# mainboard.net
KiCad netlist of a schematic drawn in EAGLE
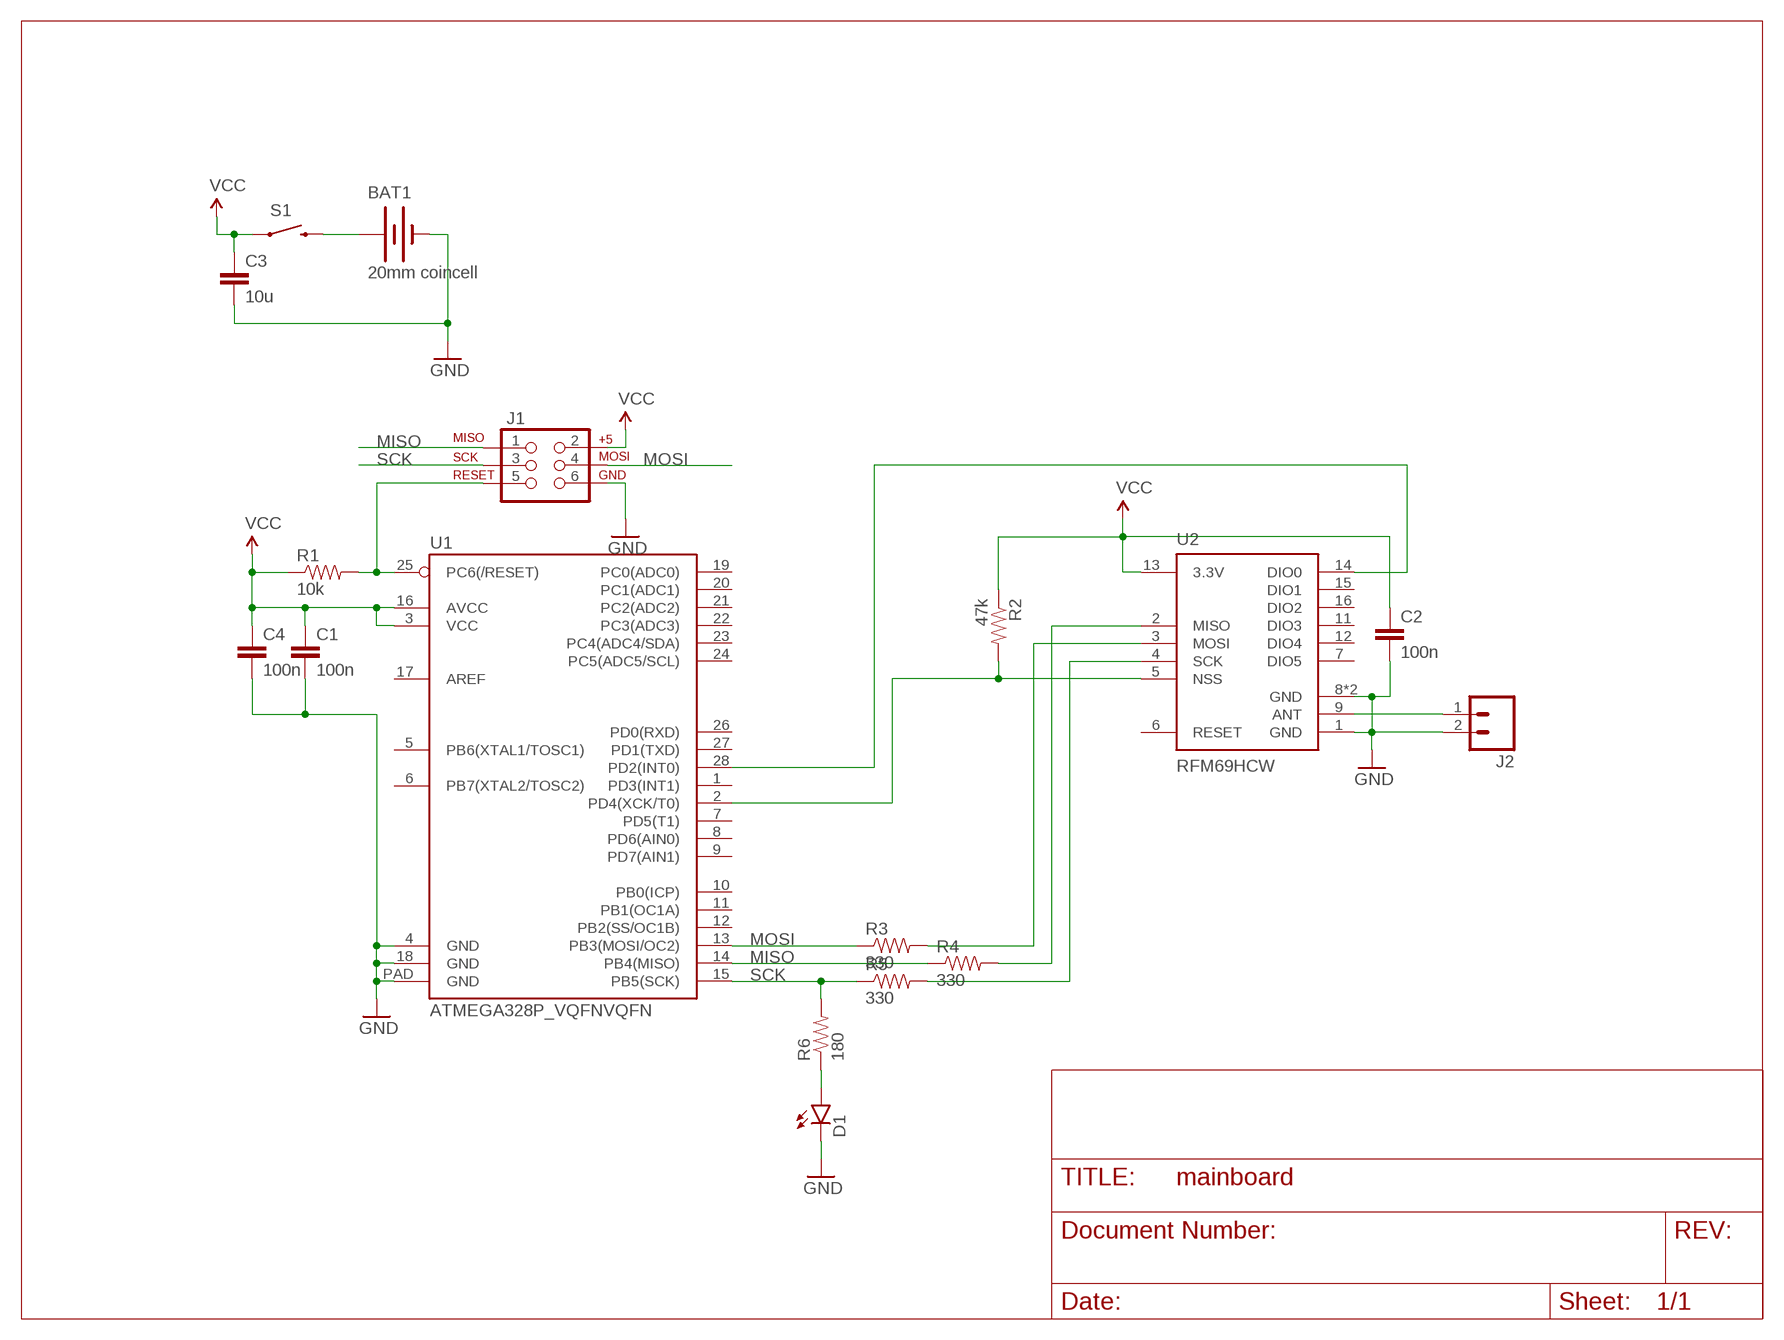
[diagram p0: schematic, sheet 1]

(export (version "E")
  (design (tool "Eeschema 10.0.6"))
  (components
    (comp (ref "BAT1")
      (value "20mm coincell")
      (footprint "eagle-import:BATTCON_20MM_4LEGS")
      (libsource (lib "eagle-import") (part "BATTERY20MM_4LEGS"))
    )
    (comp (ref "C1")
      (value "100n")
      (footprint "eagle-import:0603-CAP")
      (libsource (lib "eagle-import") (part "CAP0603-CAP"))
    )
    (comp (ref "C2")
      (value "100n")
      (footprint "eagle-import:0603-CAP")
      (libsource (lib "eagle-import") (part "CAP0603-CAP"))
    )
    (comp (ref "C3")
      (value "10u")
      (footprint "eagle-import:1206")
      (libsource (lib "eagle-import") (part "CAP1206"))
    )
    (comp (ref "C4")
      (value "100n")
      (footprint "eagle-import:0603-CAP")
      (libsource (lib "eagle-import") (part "CAP0603-CAP"))
    )
    (comp (ref "D1")
      (value "LED0603")
      (footprint "eagle-import:LED-0603")
      (libsource (lib "eagle-import") (part "LED0603"))
    )
    (comp (ref "J1")
      (value "AVR_SPI_PRG_6PTH")
      (footprint "eagle-import:2X3")
      (libsource (lib "eagle-import") (part "AVR_SPI_PRG_6PTH"))
    )
    (comp (ref "J2")
      (value "M02PTH")
      (footprint "eagle-import:1X02")
      (libsource (lib "eagle-import") (part "M02PTH"))
    )
    (comp (ref "R1")
      (value "10k")
      (footprint "eagle-import:0603-RES")
      (libsource (lib "eagle-import") (part "RESISTOR0603-RES"))
    )
    (comp (ref "R2")
      (value "47k")
      (footprint "eagle-import:0603-RES")
      (libsource (lib "eagle-import") (part "RESISTOR0603-RES"))
    )
    (comp (ref "R3")
      (value "330")
      (footprint "eagle-import:0603-RES")
      (libsource (lib "eagle-import") (part "RESISTOR0603-RES"))
    )
    (comp (ref "R4")
      (value "330")
      (footprint "eagle-import:0603-RES")
      (libsource (lib "eagle-import") (part "RESISTOR0603-RES"))
    )
    (comp (ref "R5")
      (value "330")
      (footprint "eagle-import:0603-RES")
      (libsource (lib "eagle-import") (part "RESISTOR0603-RES"))
    )
    (comp (ref "R6")
      (value "180")
      (footprint "eagle-import:0603-RES")
      (libsource (lib "eagle-import") (part "RESISTOR0603-RES"))
    )
    (comp (ref "S1")
      (value "SWITCH-MOMENTARY-2PTH")
      (footprint "eagle-import:TACTILE-PTH")
      (libsource (lib "eagle-import") (part "SWITCH-MOMENTARY-2PTH"))
    )
    (comp (ref "U1")
      (value "ATMEGA328P_VQFNVQFN")
      (footprint "eagle-import:VQFN-28")
      (libsource (lib "eagle-import") (part "ATMEGA328P_VQFNVQFN"))
    )
    (comp (ref "U2")
      (value "RFM69HCW")
      (footprint "eagle-import:RFM69HCW-XXXS2")
      (libsource (lib "eagle-import") (part "RFM69HCW"))
    )
  )
  (nets
    (net (code "1") (name "/MISO") (class "Default")
      (node (ref "J1") (pin "1") (pinfunction "1_1") (pintype "passive"))
      (node (ref "R4") (pin "1") (pinfunction "1_1") (pintype "passive"))
      (node (ref "U1") (pin "14") (pinfunction "PB4(MISO)_14") (pintype "bidirectional"))
    )
    (net (code "2") (name "/MOSI") (class "Default")
      (node (ref "J1") (pin "4") (pinfunction "4_4") (pintype "passive"))
      (node (ref "R3") (pin "1") (pinfunction "1_1") (pintype "passive"))
      (node (ref "U1") (pin "13") (pinfunction "PB3(MOSI/OC2)_13") (pintype "bidirectional"))
    )
    (net (code "3") (name "/SCK") (class "Default")
      (node (ref "J1") (pin "3") (pinfunction "3_3") (pintype "passive"))
      (node (ref "R5") (pin "1") (pinfunction "1_1") (pintype "passive"))
      (node (ref "R6") (pin "2") (pinfunction "2_2") (pintype "passive"))
      (node (ref "U1") (pin "15") (pinfunction "PB5(SCK)_15") (pintype "bidirectional"))
    )
    (net (code "4") (name "GND") (class "Default")
      (node (ref "BAT1") (pin "NEGATIVE") (pinfunction "-_NEGATIVE") (pintype "power_in"))
      (node (ref "C1") (pin "2") (pinfunction "2_2") (pintype "passive"))
      (node (ref "C2") (pin "2") (pinfunction "2_2") (pintype "passive"))
      (node (ref "C3") (pin "2") (pinfunction "2_2") (pintype "passive"))
      (node (ref "C4") (pin "2") (pinfunction "2_2") (pintype "passive"))
      (node (ref "D1") (pin "C") (pinfunction "C_C") (pintype "passive"))
      (node (ref "J1") (pin "6") (pinfunction "6_6") (pintype "passive"))
      (node (ref "J2") (pin "2") (pinfunction "2_2") (pintype "passive"))
      (node (ref "U1") (pin "18") (pinfunction "GND_18") (pintype "bidirectional"))
      (node (ref "U1") (pin "4") (pinfunction "GND_4") (pintype "bidirectional"))
      (node (ref "U1") (pin "PAD") (pinfunction "GND_PAD") (pintype "bidirectional"))
      (node (ref "U2") (pin "1") (pinfunction "GND_1") (pintype "power_in"))
      (node (ref "U2") (pin "10") (pinfunction "GND_10") (pintype "power_in"))
      (node (ref "U2") (pin "8") (pinfunction "GND_8") (pintype "power_in"))
    )
    (net (code "5") (name "Net-(D1-PadA)") (class "Default")
      (node (ref "D1") (pin "A") (pinfunction "A_A") (pintype "passive"))
      (node (ref "R6") (pin "1") (pinfunction "1_1") (pintype "passive"))
    )
    (net (code "6") (name "Net-(S1-2)") (class "Default")
      (node (ref "BAT1") (pin "POSITIVE@1") (pinfunction "+_POSITIVE@1") (pintype "power_in"))
      (node (ref "BAT1") (pin "POSITIVE@2") (pinfunction "+_POSITIVE@2") (pintype "power_in"))
      (node (ref "BAT1") (pin "POSITIVE@3") (pinfunction "+_POSITIVE@3") (pintype "power_in"))
      (node (ref "BAT1") (pin "POSITIVE@4") (pinfunction "+_POSITIVE@4") (pintype "power_in"))
      (node (ref "S1") (pin "3") (pinfunction "2_3") (pintype "passive"))
    )
    (net (code "7") (name "Net-(U1-PC6({slash}RESET))") (class "Default")
      (node (ref "J1") (pin "5") (pinfunction "5_5") (pintype "passive"))
      (node (ref "R1") (pin "2") (pinfunction "2_2") (pintype "passive"))
      (node (ref "U1") (pin "25") (pinfunction "PC6(/RESET)_25") (pintype "bidirectional"))
    )
    (net (code "8") (name "Net-(U1-PD2(INT0))") (class "Default")
      (node (ref "U1") (pin "28") (pinfunction "PD2(INT0)_28") (pintype "bidirectional"))
      (node (ref "U2") (pin "14") (pinfunction "DIO0_14") (pintype "bidirectional"))
    )
    (net (code "9") (name "Net-(U1-PD4(XCK{slash}T0))") (class "Default")
      (node (ref "R2") (pin "2") (pinfunction "2_2") (pintype "passive"))
      (node (ref "U1") (pin "2") (pinfunction "PD4(XCK/T0)_2") (pintype "bidirectional"))
      (node (ref "U2") (pin "5") (pinfunction "NSS_5") (pintype "input"))
    )
    (net (code "10") (name "Net-(U2-ANT)") (class "Default")
      (node (ref "J2") (pin "1") (pinfunction "1_1") (pintype "passive"))
      (node (ref "U2") (pin "9") (pinfunction "ANT_9") (pintype "passive"))
    )
    (net (code "11") (name "Net-(U2-MISO)") (class "Default")
      (node (ref "R4") (pin "2") (pinfunction "2_2") (pintype "passive"))
      (node (ref "U2") (pin "2") (pinfunction "MISO_2") (pintype "bidirectional"))
    )
    (net (code "12") (name "Net-(U2-MOSI)") (class "Default")
      (node (ref "R3") (pin "2") (pinfunction "2_2") (pintype "passive"))
      (node (ref "U2") (pin "3") (pinfunction "MOSI_3") (pintype "input"))
    )
    (net (code "13") (name "Net-(U2-SCK)") (class "Default")
      (node (ref "R5") (pin "2") (pinfunction "2_2") (pintype "passive"))
      (node (ref "U2") (pin "4") (pinfunction "SCK_4") (pintype "input"))
    )
    (net (code "14") (name "VCC") (class "Default")
      (node (ref "C1") (pin "1") (pinfunction "1_1") (pintype "passive"))
      (node (ref "C2") (pin "1") (pinfunction "1_1") (pintype "passive"))
      (node (ref "C3") (pin "1") (pinfunction "1_1") (pintype "passive"))
      (node (ref "C4") (pin "1") (pinfunction "1_1") (pintype "passive"))
      (node (ref "J1") (pin "2") (pinfunction "2_2") (pintype "passive"))
      (node (ref "R1") (pin "1") (pinfunction "1_1") (pintype "passive"))
      (node (ref "R2") (pin "1") (pinfunction "1_1") (pintype "passive"))
      (node (ref "S1") (pin "1") (pinfunction "1_1") (pintype "passive"))
      (node (ref "U1") (pin "16") (pinfunction "AVCC_16") (pintype "bidirectional"))
      (node (ref "U1") (pin "3") (pinfunction "VCC_3") (pintype "bidirectional"))
      (node (ref "U2") (pin "13") (pinfunction "3.3V_13") (pintype "power_in"))
    )
    (net (code "15") (name "unconnected-(U1-AREF-Pad17)") (class "Default")
      (node (ref "U1") (pin "17") (pinfunction "AREF_17") (pintype "bidirectional"))
    )
    (net (code "16") (name "unconnected-(U1-PB0(ICP)-Pad10)") (class "Default")
      (node (ref "U1") (pin "10") (pinfunction "PB0(ICP)_10") (pintype "bidirectional"))
    )
    (net (code "17") (name "unconnected-(U1-PB1(OC1A)-Pad11)") (class "Default")
      (node (ref "U1") (pin "11") (pinfunction "PB1(OC1A)_11") (pintype "bidirectional"))
    )
    (net (code "18") (name "unconnected-(U1-PB2(SS{slash}OC1B)-Pad12)") (class "Default")
      (node (ref "U1") (pin "12") (pinfunction "PB2(SS/OC1B)_12") (pintype "bidirectional"))
    )
    (net (code "19") (name "unconnected-(U1-PB6(XTAL1{slash}TOSC1)-Pad5)") (class "Default")
      (node (ref "U1") (pin "5") (pinfunction "PB6(XTAL1/TOSC1)_5") (pintype "bidirectional"))
    )
    (net (code "20") (name "unconnected-(U1-PB7(XTAL2{slash}TOSC2)-Pad6)") (class "Default")
      (node (ref "U1") (pin "6") (pinfunction "PB7(XTAL2/TOSC2)_6") (pintype "bidirectional"))
    )
    (net (code "21") (name "unconnected-(U1-PC0(ADC0)-Pad19)") (class "Default")
      (node (ref "U1") (pin "19") (pinfunction "PC0(ADC0)_19") (pintype "bidirectional"))
    )
    (net (code "22") (name "unconnected-(U1-PC1(ADC1)-Pad20)") (class "Default")
      (node (ref "U1") (pin "20") (pinfunction "PC1(ADC1)_20") (pintype "bidirectional"))
    )
    (net (code "23") (name "unconnected-(U1-PC2(ADC2)-Pad21)") (class "Default")
      (node (ref "U1") (pin "21") (pinfunction "PC2(ADC2)_21") (pintype "bidirectional"))
    )
    (net (code "24") (name "unconnected-(U1-PC3(ADC3)-Pad22)") (class "Default")
      (node (ref "U1") (pin "22") (pinfunction "PC3(ADC3)_22") (pintype "bidirectional"))
    )
    (net (code "25") (name "unconnected-(U1-PC4(ADC4{slash}SDA)-Pad23)") (class "Default")
      (node (ref "U1") (pin "23") (pinfunction "PC4(ADC4/SDA)_23") (pintype "bidirectional"))
    )
    (net (code "26") (name "unconnected-(U1-PC5(ADC5{slash}SCL)-Pad24)") (class "Default")
      (node (ref "U1") (pin "24") (pinfunction "PC5(ADC5/SCL)_24") (pintype "bidirectional"))
    )
    (net (code "27") (name "unconnected-(U1-PD0(RXD)-Pad26)") (class "Default")
      (node (ref "U1") (pin "26") (pinfunction "PD0(RXD)_26") (pintype "bidirectional"))
    )
    (net (code "28") (name "unconnected-(U1-PD1(TXD)-Pad27)") (class "Default")
      (node (ref "U1") (pin "27") (pinfunction "PD1(TXD)_27") (pintype "bidirectional"))
    )
    (net (code "29") (name "unconnected-(U1-PD3(INT1)-Pad1)") (class "Default")
      (node (ref "U1") (pin "1") (pinfunction "PD3(INT1)_1") (pintype "bidirectional"))
    )
    (net (code "30") (name "unconnected-(U1-PD5(T1)-Pad7)") (class "Default")
      (node (ref "U1") (pin "7") (pinfunction "PD5(T1)_7") (pintype "bidirectional"))
    )
    (net (code "31") (name "unconnected-(U1-PD6(AIN0)-Pad8)") (class "Default")
      (node (ref "U1") (pin "8") (pinfunction "PD6(AIN0)_8") (pintype "bidirectional"))
    )
    (net (code "32") (name "unconnected-(U1-PD7(AIN1)-Pad9)") (class "Default")
      (node (ref "U1") (pin "9") (pinfunction "PD7(AIN1)_9") (pintype "bidirectional"))
    )
    (net (code "33") (name "unconnected-(U2-DIO1-Pad15)") (class "Default")
      (node (ref "U2") (pin "15") (pinfunction "DIO1_15") (pintype "bidirectional"))
    )
    (net (code "34") (name "unconnected-(U2-DIO2-Pad16)") (class "Default")
      (node (ref "U2") (pin "16") (pinfunction "DIO2_16") (pintype "bidirectional"))
    )
    (net (code "35") (name "unconnected-(U2-DIO3-Pad11)") (class "Default")
      (node (ref "U2") (pin "11") (pinfunction "DIO3_11") (pintype "bidirectional"))
    )
    (net (code "36") (name "unconnected-(U2-DIO4-Pad12)") (class "Default")
      (node (ref "U2") (pin "12") (pinfunction "DIO4_12") (pintype "bidirectional"))
    )
    (net (code "37") (name "unconnected-(U2-DIO5-Pad7)") (class "Default")
      (node (ref "U2") (pin "7") (pinfunction "DIO5_7") (pintype "bidirectional"))
    )
    (net (code "38") (name "unconnected-(U2-RESET-Pad6)") (class "Default")
      (node (ref "U2") (pin "6") (pinfunction "RESET_6") (pintype "input"))
    )
  )
)
